# 06_-_Voltage_Sense.net
KiCad netlist of a schematic drawn in Altium Designer
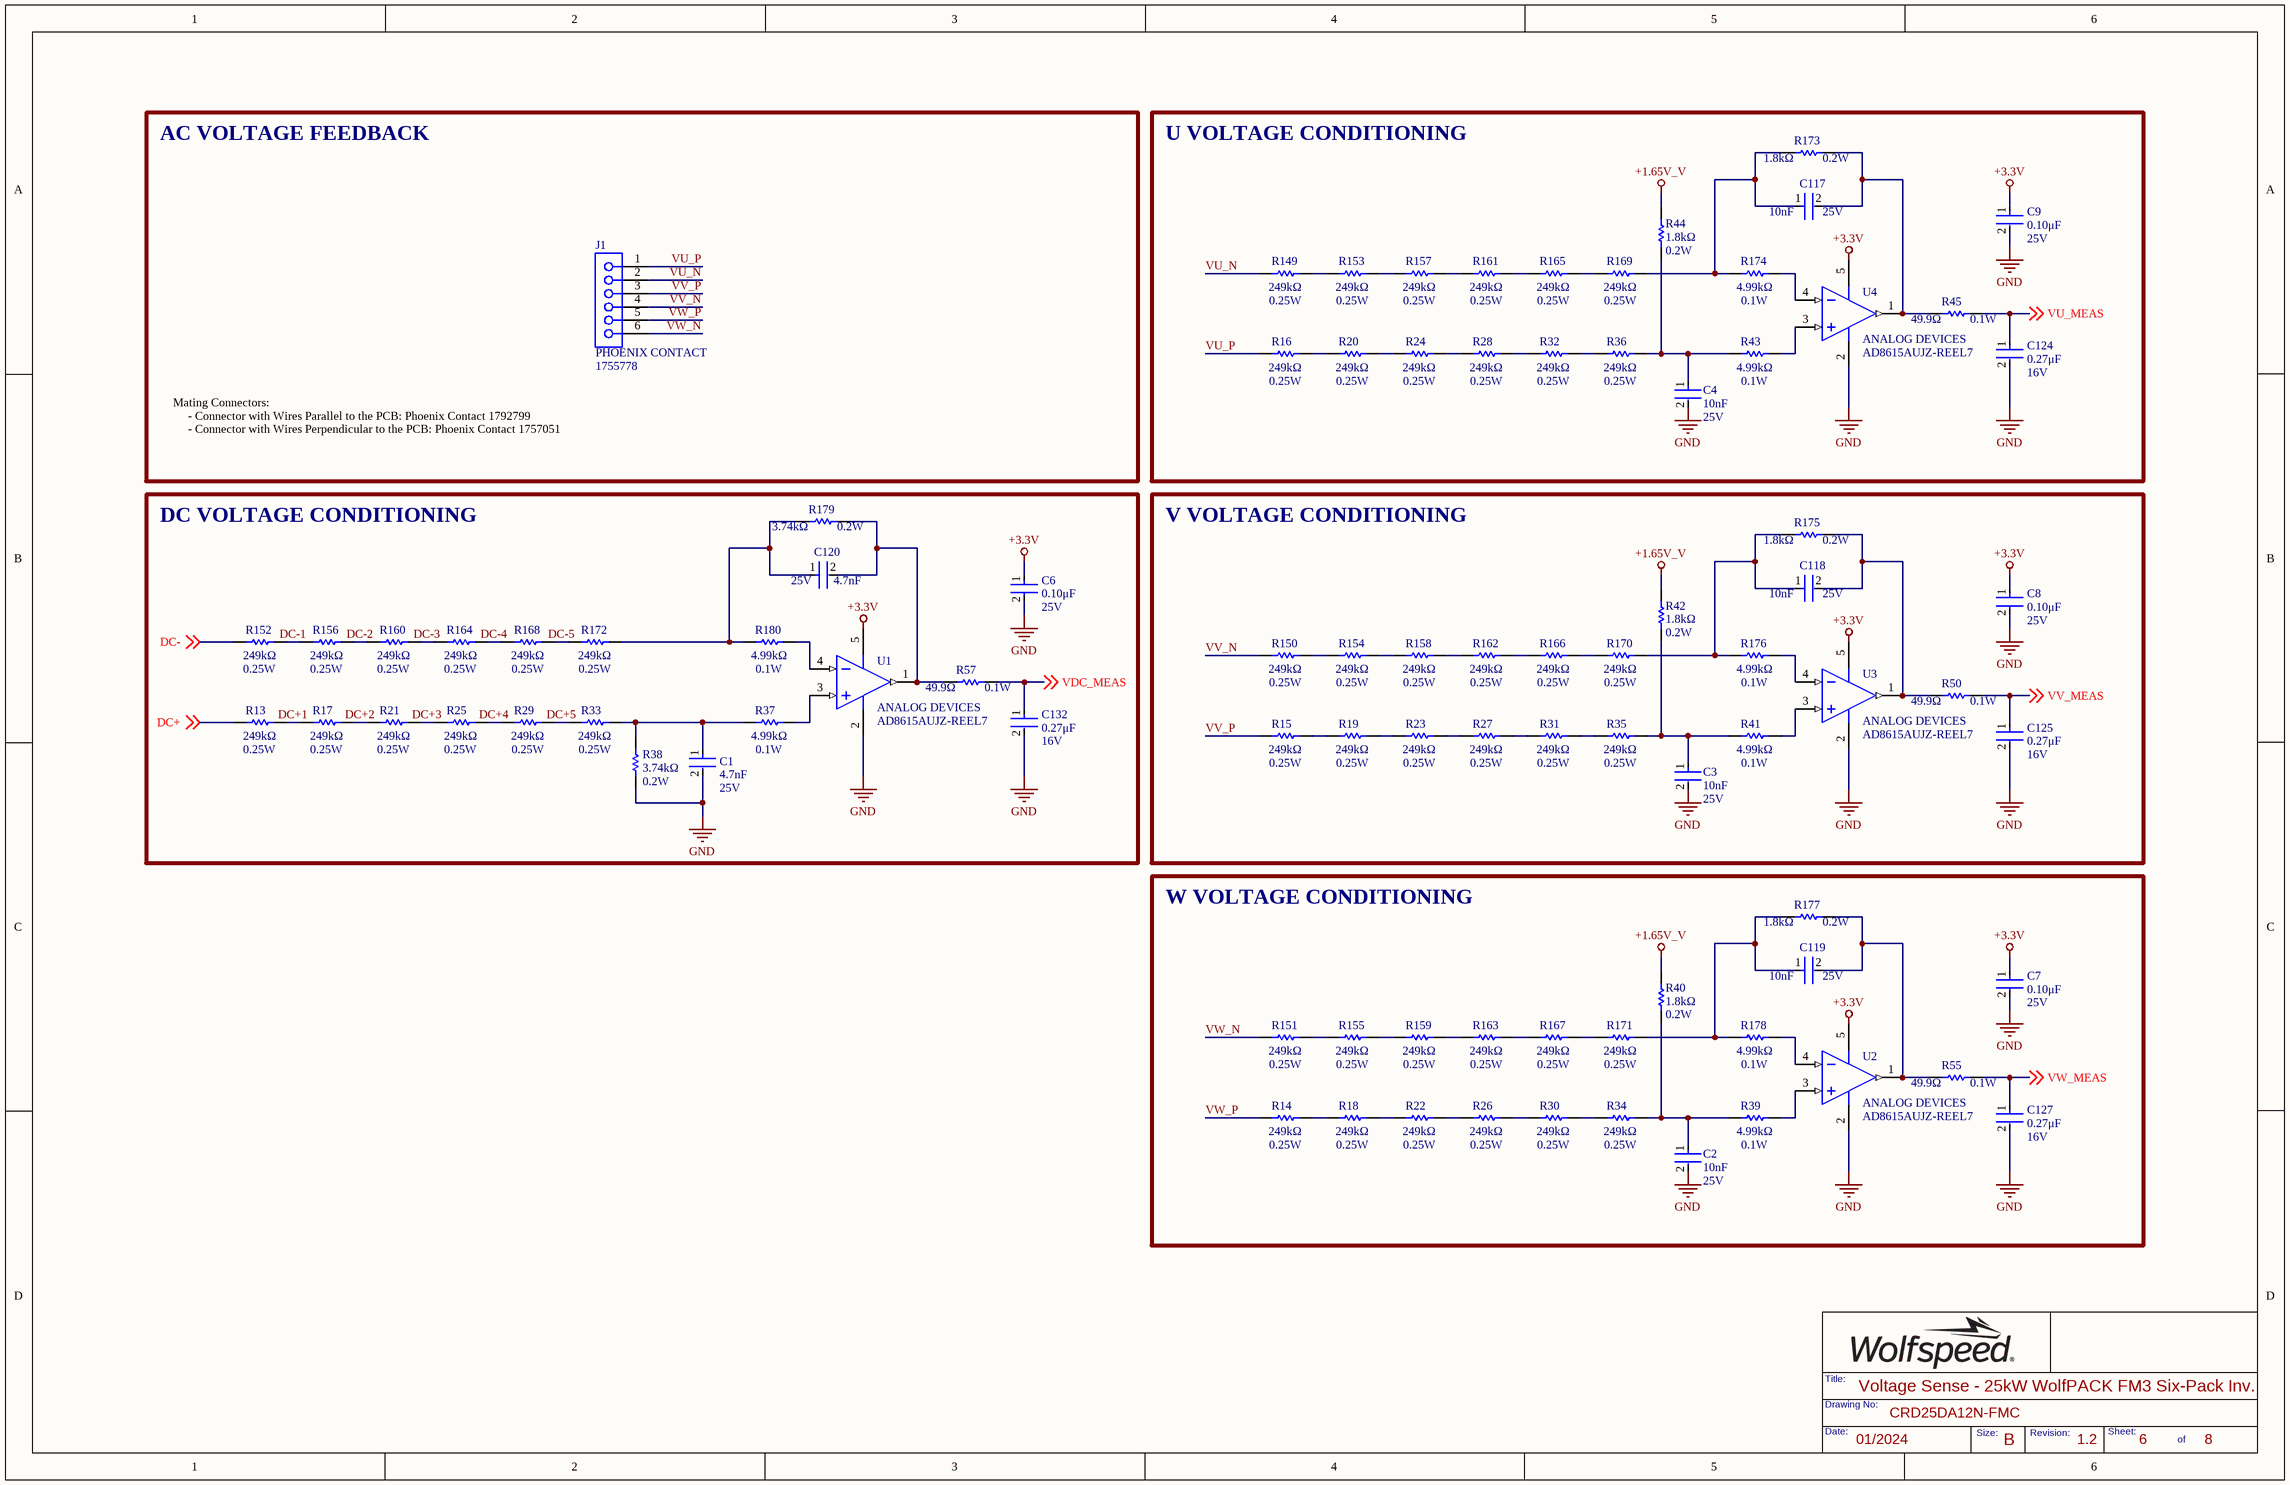
[diagram p0: 06 - Voltage Sense.SchDoc]

(export (version "E")
  (design (tool "Eeschema 10.0.6"))
  (components
    (comp (ref "C1")
      (value "C0603C472K3RAC7867")
      (footprint "FP-C0603C-CF-IPC_B")
      (description "CAP CER 4700PF 25V 10% X7R 0603")
      (fields
        (field (name "MANUFACTURER") "KEMET")
        (field (name "MANUFACTURER PART NUMBER") "C0603C472K3RACTU")
        (field (name "VOLTAGE RATING") "25V")
        (field (name "CAPACITANCE") "4.7nF")
      )
      (libsource (lib "Inverter_25kW") (part "C0603C472K3RAC7867"))
    )
    (comp (ref "C2")
      (value "10nF")
      (footprint "FP-C0603C-CF-IPC_B")
      (description "CAP CER 10000PF 25V X7R 0603")
      (fields
        (field (name "MANUFACTURER") "SAMSUNG")
        (field (name "MANUFACTURER PART NUMBER") "CL10B103KA8WPNC")
        (field (name "VOLTAGE RATING") "25V")
      )
      (libsource (lib "Inverter_25kW") (part "CL10B103KA8WPNC"))
    )
    (comp (ref "C3")
      (value "10nF")
      (footprint "FP-C0603C-CF-IPC_B")
      (description "CAP CER 10000PF 25V X7R 0603")
      (fields
        (field (name "MANUFACTURER") "SAMSUNG")
        (field (name "MANUFACTURER PART NUMBER") "CL10B103KA8WPNC")
        (field (name "VOLTAGE RATING") "25V")
      )
      (libsource (lib "Inverter_25kW") (part "CL10B103KA8WPNC"))
    )
    (comp (ref "C4")
      (value "10nF")
      (footprint "FP-C0603C-CF-IPC_B")
      (description "CAP CER 10000PF 25V X7R 0603")
      (fields
        (field (name "MANUFACTURER") "SAMSUNG")
        (field (name "MANUFACTURER PART NUMBER") "CL10B103KA8WPNC")
        (field (name "VOLTAGE RATING") "25V")
      )
      (libsource (lib "Inverter_25kW") (part "CL10B103KA8WPNC"))
    )
    (comp (ref "C6")
      (value "C0603C104K3RACTU")
      (footprint "FP-C0603C-CF-IPC_B")
      (description "CAP CER 0.1UF 25V X7R 0603")
      (fields
        (field (name "VOLTAGE RATING") "25V")
        (field (name "OCTOPART") "https://octopart.com/c0603c104k3ractu-kemet-127541")
        (field (name "MANUFACTURER") "KEMET")
        (field (name "CAPACITANCE") "0.10μF")
      )
      (libsource (lib "Altium Content Vault") (part "b4654b650e69147ec39a6b967a45e02"))
    )
    (comp (ref "C7")
      (value "C0603C104K3RACTU")
      (footprint "FP-C0603C-CF-IPC_B")
      (description "CAP CER 0.1UF 25V X7R 0603")
      (fields
        (field (name "VOLTAGE RATING") "25V")
        (field (name "OCTOPART") "https://octopart.com/c0603c104k3ractu-kemet-127541")
        (field (name "MANUFACTURER") "KEMET")
        (field (name "CAPACITANCE") "0.10μF")
      )
      (libsource (lib "Altium Content Vault") (part "b4654b650e69147ec39a6b967a45e02"))
    )
    (comp (ref "C8")
      (value "C0603C104K3RACTU")
      (footprint "FP-C0603C-CF-IPC_B")
      (description "CAP CER 0.1UF 25V X7R 0603")
      (fields
        (field (name "VOLTAGE RATING") "25V")
        (field (name "OCTOPART") "https://octopart.com/c0603c104k3ractu-kemet-127541")
        (field (name "MANUFACTURER") "KEMET")
        (field (name "CAPACITANCE") "0.10μF")
      )
      (libsource (lib "Altium Content Vault") (part "b4654b650e69147ec39a6b967a45e02"))
    )
    (comp (ref "C9")
      (value "C0603C104K3RACTU")
      (footprint "FP-C0603C-CF-IPC_B")
      (description "CAP CER 0.1UF 25V X7R 0603")
      (fields
        (field (name "VOLTAGE RATING") "25V")
        (field (name "OCTOPART") "https://octopart.com/c0603c104k3ractu-kemet-127541")
        (field (name "MANUFACTURER") "KEMET")
        (field (name "CAPACITANCE") "0.10μF")
      )
      (libsource (lib "Altium Content Vault") (part "b4654b650e69147ec39a6b967a45e02"))
    )
    (comp (ref "C117")
      (value "10nF")
      (footprint "FP-C0603C-CF-IPC_B")
      (description "CAP CER 10000PF 25V X7R 0603")
      (fields
        (field (name "MANUFACTURER") "SAMSUNG")
        (field (name "MANUFACTURER PART NUMBER") "CL10B103KA8WPNC")
        (field (name "VOLTAGE RATING") "25V")
      )
      (libsource (lib "Inverter_25kW") (part "CL10B103KA8WPNC"))
    )
    (comp (ref "C118")
      (value "10nF")
      (footprint "FP-C0603C-CF-IPC_B")
      (description "CAP CER 10000PF 25V X7R 0603")
      (fields
        (field (name "MANUFACTURER") "SAMSUNG")
        (field (name "MANUFACTURER PART NUMBER") "CL10B103KA8WPNC")
        (field (name "VOLTAGE RATING") "25V")
      )
      (libsource (lib "Inverter_25kW") (part "CL10B103KA8WPNC"))
    )
    (comp (ref "C119")
      (value "10nF")
      (footprint "FP-C0603C-CF-IPC_B")
      (description "CAP CER 10000PF 25V X7R 0603")
      (fields
        (field (name "MANUFACTURER") "SAMSUNG")
        (field (name "MANUFACTURER PART NUMBER") "CL10B103KA8WPNC")
        (field (name "VOLTAGE RATING") "25V")
      )
      (libsource (lib "Inverter_25kW") (part "CL10B103KA8WPNC"))
    )
    (comp (ref "C120")
      (value "C0603C472K3RAC7867")
      (footprint "FP-C0603C-CF-IPC_B")
      (description "CAP CER 4700PF 25V 10% X7R 0603")
      (fields
        (field (name "MANUFACTURER") "KEMET")
        (field (name "MANUFACTURER PART NUMBER") "C0603C472K3RACTU")
        (field (name "VOLTAGE RATING") "25V")
        (field (name "CAPACITANCE") "4.7nF")
      )
      (libsource (lib "Inverter_25kW") (part "C0603C472K3RAC7867"))
    )
    (comp (ref "C124")
      (value "GCM188R71C274KA37D")
      (footprint "FP-GCM188-0_1-IPC_A")
      (description "CAP CER 0.27UF 16V X7R 0603")
      (fields
        (field (name "VOLTAGE RATING (DC)") "16V")
        (field (name "CAPACITANCE") "0.27μF")
        (field (name "TOLERANCE") "10%")
        (field (name "MANUFACTURER") "MURATA")
      )
      (libsource (lib "Altium Content Vault") (part "02cd4be3c70576c341d710602a673aa"))
    )
    (comp (ref "C125")
      (value "GCM188R71C274KA37D")
      (footprint "FP-GCM188-0_1-IPC_A")
      (description "CAP CER 0.27UF 16V X7R 0603")
      (fields
        (field (name "VOLTAGE RATING (DC)") "16V")
        (field (name "CAPACITANCE") "0.27μF")
        (field (name "TOLERANCE") "10%")
        (field (name "MANUFACTURER") "MURATA")
      )
      (libsource (lib "Altium Content Vault") (part "02cd4be3c70576c341d710602a673aa"))
    )
    (comp (ref "C127")
      (value "GCM188R71C274KA37D")
      (footprint "FP-GCM188-0_1-IPC_A")
      (description "CAP CER 0.27UF 16V X7R 0603")
      (fields
        (field (name "VOLTAGE RATING (DC)") "16V")
        (field (name "CAPACITANCE") "0.27μF")
        (field (name "TOLERANCE") "10%")
        (field (name "MANUFACTURER") "MURATA")
      )
      (libsource (lib "Altium Content Vault") (part "02cd4be3c70576c341d710602a673aa"))
    )
    (comp (ref "C132")
      (value "GCM188R71C274KA37D")
      (footprint "FP-GCM188-0_1-IPC_A")
      (description "CAP CER 0.27UF 16V X7R 0603")
      (fields
        (field (name "VOLTAGE RATING (DC)") "16V")
        (field (name "CAPACITANCE") "0.27μF")
        (field (name "TOLERANCE") "10%")
        (field (name "MANUFACTURER") "MURATA")
      )
      (libsource (lib "Altium Content Vault") (part "02cd4be3c70576c341d710602a673aa"))
    )
    (comp (ref "J1")
      (value "1755778")
      (footprint "Inverter_25kW:1755778")
      (description "TERM BLOCK HDR 6POS VERT 5.08MM")
      (fields
        (field (name "MANUFACTURER") "PHOENIX CONTACT")
        (field (name "VOLTAGE") "300V")
        (field (name "MANUFACTURER PRINT") "PHOENIX CONTACT")
      )
      (libsource (lib "Inverter_25kW") (part "1755778"))
    )
    (comp (ref "R13")
      (value "TNPW1206249KBEEA")
      (footprint "RESC3216X65X50NL15T25")
      (description "RES 249K OHM 0.1% 1/4W 1206")
      (fields
        (field (name "MANUFACTURER") "VISHAY DALE")
        (field (name "RESISTANCE") "249kΩ")
        (field (name "POWER") "0.25W")
      )
      (libsource (lib "Altium Content Vault") (part "RES"))
    )
    (comp (ref "R14")
      (value "TNPW1206249KBEEA")
      (footprint "RESC3216X65X50NL15T25")
      (description "RES 249K OHM 0.1% 1/4W 1206")
      (fields
        (field (name "MANUFACTURER") "VISHAY DALE")
        (field (name "RESISTANCE") "249kΩ")
        (field (name "POWER") "0.25W")
      )
      (libsource (lib "Altium Content Vault") (part "RES"))
    )
    (comp (ref "R15")
      (value "TNPW1206249KBEEA")
      (footprint "RESC3216X65X50NL15T25")
      (description "RES 249K OHM 0.1% 1/4W 1206")
      (fields
        (field (name "MANUFACTURER") "VISHAY DALE")
        (field (name "RESISTANCE") "249kΩ")
        (field (name "POWER") "0.25W")
      )
      (libsource (lib "Altium Content Vault") (part "RES"))
    )
    (comp (ref "R16")
      (value "TNPW1206249KBEEA")
      (footprint "RESC3216X65X50NL15T25")
      (description "RES 249K OHM 0.1% 1/4W 1206")
      (fields
        (field (name "MANUFACTURER") "VISHAY DALE")
        (field (name "RESISTANCE") "249kΩ")
        (field (name "POWER") "0.25W")
      )
      (libsource (lib "Altium Content Vault") (part "RES"))
    )
    (comp (ref "R17")
      (value "TNPW1206249KBEEA")
      (footprint "RESC3216X65X50NL15T25")
      (description "RES 249K OHM 0.1% 1/4W 1206")
      (fields
        (field (name "MANUFACTURER") "VISHAY DALE")
        (field (name "RESISTANCE") "249kΩ")
        (field (name "POWER") "0.25W")
      )
      (libsource (lib "Altium Content Vault") (part "RES"))
    )
    (comp (ref "R18")
      (value "TNPW1206249KBEEA")
      (footprint "RESC3216X65X50NL15T25")
      (description "RES 249K OHM 0.1% 1/4W 1206")
      (fields
        (field (name "MANUFACTURER") "VISHAY DALE")
        (field (name "RESISTANCE") "249kΩ")
        (field (name "POWER") "0.25W")
      )
      (libsource (lib "Altium Content Vault") (part "RES"))
    )
    (comp (ref "R19")
      (value "TNPW1206249KBEEA")
      (footprint "RESC3216X65X50NL15T25")
      (description "RES 249K OHM 0.1% 1/4W 1206")
      (fields
        (field (name "MANUFACTURER") "VISHAY DALE")
        (field (name "RESISTANCE") "249kΩ")
        (field (name "POWER") "0.25W")
      )
      (libsource (lib "Altium Content Vault") (part "RES"))
    )
    (comp (ref "R20")
      (value "TNPW1206249KBEEA")
      (footprint "RESC3216X65X50NL15T25")
      (description "RES 249K OHM 0.1% 1/4W 1206")
      (fields
        (field (name "MANUFACTURER") "VISHAY DALE")
        (field (name "RESISTANCE") "249kΩ")
        (field (name "POWER") "0.25W")
      )
      (libsource (lib "Altium Content Vault") (part "RES"))
    )
    (comp (ref "R21")
      (value "TNPW1206249KBEEA")
      (footprint "RESC3216X65X50NL15T25")
      (description "RES 249K OHM 0.1% 1/4W 1206")
      (fields
        (field (name "MANUFACTURER") "VISHAY DALE")
        (field (name "RESISTANCE") "249kΩ")
        (field (name "POWER") "0.25W")
      )
      (libsource (lib "Altium Content Vault") (part "RES"))
    )
    (comp (ref "R22")
      (value "TNPW1206249KBEEA")
      (footprint "RESC3216X65X50NL15T25")
      (description "RES 249K OHM 0.1% 1/4W 1206")
      (fields
        (field (name "MANUFACTURER") "VISHAY DALE")
        (field (name "RESISTANCE") "249kΩ")
        (field (name "POWER") "0.25W")
      )
      (libsource (lib "Altium Content Vault") (part "RES"))
    )
    (comp (ref "R23")
      (value "TNPW1206249KBEEA")
      (footprint "RESC3216X65X50NL15T25")
      (description "RES 249K OHM 0.1% 1/4W 1206")
      (fields
        (field (name "MANUFACTURER") "VISHAY DALE")
        (field (name "RESISTANCE") "249kΩ")
        (field (name "POWER") "0.25W")
      )
      (libsource (lib "Altium Content Vault") (part "RES"))
    )
    (comp (ref "R24")
      (value "TNPW1206249KBEEA")
      (footprint "RESC3216X65X50NL15T25")
      (description "RES 249K OHM 0.1% 1/4W 1206")
      (fields
        (field (name "MANUFACTURER") "VISHAY DALE")
        (field (name "RESISTANCE") "249kΩ")
        (field (name "POWER") "0.25W")
      )
      (libsource (lib "Altium Content Vault") (part "RES"))
    )
    (comp (ref "R25")
      (value "TNPW1206249KBEEA")
      (footprint "RESC3216X65X50NL15T25")
      (description "RES 249K OHM 0.1% 1/4W 1206")
      (fields
        (field (name "MANUFACTURER") "VISHAY DALE")
        (field (name "RESISTANCE") "249kΩ")
        (field (name "POWER") "0.25W")
      )
      (libsource (lib "Altium Content Vault") (part "RES"))
    )
    (comp (ref "R26")
      (value "TNPW1206249KBEEA")
      (footprint "RESC3216X65X50NL15T25")
      (description "RES 249K OHM 0.1% 1/4W 1206")
      (fields
        (field (name "MANUFACTURER") "VISHAY DALE")
        (field (name "RESISTANCE") "249kΩ")
        (field (name "POWER") "0.25W")
      )
      (libsource (lib "Altium Content Vault") (part "RES"))
    )
    (comp (ref "R27")
      (value "TNPW1206249KBEEA")
      (footprint "RESC3216X65X50NL15T25")
      (description "RES 249K OHM 0.1% 1/4W 1206")
      (fields
        (field (name "MANUFACTURER") "VISHAY DALE")
        (field (name "RESISTANCE") "249kΩ")
        (field (name "POWER") "0.25W")
      )
      (libsource (lib "Altium Content Vault") (part "RES"))
    )
    (comp (ref "R28")
      (value "TNPW1206249KBEEA")
      (footprint "RESC3216X65X50NL15T25")
      (description "RES 249K OHM 0.1% 1/4W 1206")
      (fields
        (field (name "MANUFACTURER") "VISHAY DALE")
        (field (name "RESISTANCE") "249kΩ")
        (field (name "POWER") "0.25W")
      )
      (libsource (lib "Altium Content Vault") (part "RES"))
    )
    (comp (ref "R29")
      (value "TNPW1206249KBEEA")
      (footprint "RESC3216X65X50NL15T25")
      (description "RES 249K OHM 0.1% 1/4W 1206")
      (fields
        (field (name "MANUFACTURER") "VISHAY DALE")
        (field (name "RESISTANCE") "249kΩ")
        (field (name "POWER") "0.25W")
      )
      (libsource (lib "Altium Content Vault") (part "RES"))
    )
    (comp (ref "R30")
      (value "TNPW1206249KBEEA")
      (footprint "RESC3216X65X50NL15T25")
      (description "RES 249K OHM 0.1% 1/4W 1206")
      (fields
        (field (name "MANUFACTURER") "VISHAY DALE")
        (field (name "RESISTANCE") "249kΩ")
        (field (name "POWER") "0.25W")
      )
      (libsource (lib "Altium Content Vault") (part "RES"))
    )
    (comp (ref "R31")
      (value "TNPW1206249KBEEA")
      (footprint "RESC3216X65X50NL15T25")
      (description "RES 249K OHM 0.1% 1/4W 1206")
      (fields
        (field (name "MANUFACTURER") "VISHAY DALE")
        (field (name "RESISTANCE") "249kΩ")
        (field (name "POWER") "0.25W")
      )
      (libsource (lib "Altium Content Vault") (part "RES"))
    )
    (comp (ref "R32")
      (value "TNPW1206249KBEEA")
      (footprint "RESC3216X65X50NL15T25")
      (description "RES 249K OHM 0.1% 1/4W 1206")
      (fields
        (field (name "MANUFACTURER") "VISHAY DALE")
        (field (name "RESISTANCE") "249kΩ")
        (field (name "POWER") "0.25W")
      )
      (libsource (lib "Altium Content Vault") (part "RES"))
    )
    (comp (ref "R33")
      (value "TNPW1206249KBEEA")
      (footprint "RESC3216X65X50NL15T25")
      (description "RES 249K OHM 0.1% 1/4W 1206")
      (fields
        (field (name "MANUFACTURER") "VISHAY DALE")
        (field (name "RESISTANCE") "249kΩ")
        (field (name "POWER") "0.25W")
      )
      (libsource (lib "Altium Content Vault") (part "RES"))
    )
    (comp (ref "R34")
      (value "TNPW1206249KBEEA")
      (footprint "RESC3216X65X50NL15T25")
      (description "RES 249K OHM 0.1% 1/4W 1206")
      (fields
        (field (name "MANUFACTURER") "VISHAY DALE")
        (field (name "RESISTANCE") "249kΩ")
        (field (name "POWER") "0.25W")
      )
      (libsource (lib "Altium Content Vault") (part "RES"))
    )
    (comp (ref "R35")
      (value "TNPW1206249KBEEA")
      (footprint "RESC3216X65X50NL15T25")
      (description "RES 249K OHM 0.1% 1/4W 1206")
      (fields
        (field (name "MANUFACTURER") "VISHAY DALE")
        (field (name "RESISTANCE") "249kΩ")
        (field (name "POWER") "0.25W")
      )
      (libsource (lib "Altium Content Vault") (part "RES"))
    )
    (comp (ref "R36")
      (value "TNPW1206249KBEEA")
      (footprint "RESC3216X65X50NL15T25")
      (description "RES 249K OHM 0.1% 1/4W 1206")
      (fields
        (field (name "MANUFACTURER") "VISHAY DALE")
        (field (name "RESISTANCE") "249kΩ")
        (field (name "POWER") "0.25W")
      )
      (libsource (lib "Altium Content Vault") (part "RES"))
    )
    (comp (ref "R37")
      (value "RC0603FR-074K99L")
      (footprint "FP-MCR03-IPC_B")
      (description "RES 4.99K OHM 1% 1/10W 0603")
      (fields
        (field (name "MANUFACTURER") "YAGEO")
        (field (name "TOLERANCE") "1%")
        (field (name "POWER RATING") "0.1W")
        (field (name "RESISTANCE") "4.99kΩ")
      )
      (libsource (lib "Inverter_25kW") (part "RC0603FR-074K99L"))
    )
    (comp (ref "R38")
      (value "ERJ-PB3B3741V")
      (footprint "FP-MCR03-IPC_B")
      (description "RES SMD 3.74K OHM 0.1% 1/5W 0603")
      (fields
        (field (name "MANUFACTURER") "PANASONIC")
        (field (name "TOLERANCE") "0.1%")
        (field (name "MAX POWER DISSIPATION") "0.2W")
        (field (name "RESISTANCE") "3.74kΩ")
      )
      (libsource (lib "Inverter_25kW") (part "ERJ-PB3B3741V"))
    )
    (comp (ref "R39")
      (value "RC0603FR-074K99L")
      (footprint "FP-MCR03-IPC_B")
      (description "RES 4.99K OHM 1% 1/10W 0603")
      (fields
        (field (name "MANUFACTURER") "YAGEO")
        (field (name "TOLERANCE") "1%")
        (field (name "POWER RATING") "0.1W")
        (field (name "RESISTANCE") "4.99kΩ")
      )
      (libsource (lib "Inverter_25kW") (part "RC0603FR-074K99L"))
    )
    (comp (ref "R40")
      (value "ERJ-PB3B1801V")
      (footprint "FP-MCR03-IPC_B")
      (description "RES SMD 1.8K OHM 0.1% 1/5W 0603")
      (fields
        (field (name "MANUFACTURER") "PANASONIC")
        (field (name "TOLERANCE") "0.1%")
        (field (name "RESISTANCE") "1.8kΩ")
        (field (name "MAX POWER DISSIPATION") "0.2W")
      )
      (libsource (lib "Inverter_25kW") (part "ERJ-PB3B1801V"))
    )
    (comp (ref "R41")
      (value "RC0603FR-074K99L")
      (footprint "FP-MCR03-IPC_B")
      (description "RES 4.99K OHM 1% 1/10W 0603")
      (fields
        (field (name "MANUFACTURER") "YAGEO")
        (field (name "TOLERANCE") "1%")
        (field (name "POWER RATING") "0.1W")
        (field (name "RESISTANCE") "4.99kΩ")
      )
      (libsource (lib "Inverter_25kW") (part "RC0603FR-074K99L"))
    )
    (comp (ref "R42")
      (value "ERJ-PB3B1801V")
      (footprint "FP-MCR03-IPC_B")
      (description "RES SMD 1.8K OHM 0.1% 1/5W 0603")
      (fields
        (field (name "MANUFACTURER") "PANASONIC")
        (field (name "TOLERANCE") "0.1%")
        (field (name "RESISTANCE") "1.8kΩ")
        (field (name "MAX POWER DISSIPATION") "0.2W")
      )
      (libsource (lib "Inverter_25kW") (part "ERJ-PB3B1801V"))
    )
    (comp (ref "R43")
      (value "RC0603FR-074K99L")
      (footprint "FP-MCR03-IPC_B")
      (description "RES 4.99K OHM 1% 1/10W 0603")
      (fields
        (field (name "MANUFACTURER") "YAGEO")
        (field (name "TOLERANCE") "1%")
        (field (name "POWER RATING") "0.1W")
        (field (name "RESISTANCE") "4.99kΩ")
      )
      (libsource (lib "Inverter_25kW") (part "RC0603FR-074K99L"))
    )
    (comp (ref "R44")
      (value "ERJ-PB3B1801V")
      (footprint "FP-MCR03-IPC_B")
      (description "RES SMD 1.8K OHM 0.1% 1/5W 0603")
      (fields
        (field (name "MANUFACTURER") "PANASONIC")
        (field (name "TOLERANCE") "0.1%")
        (field (name "RESISTANCE") "1.8kΩ")
        (field (name "MAX POWER DISSIPATION") "0.2W")
      )
      (libsource (lib "Inverter_25kW") (part "ERJ-PB3B1801V"))
    )
    (comp (ref "R45")
      (value "ERJ-3EKF49R9V")
      (footprint "FP-MCR03-IPC_B")
      (description "RES SMD 49.9 OHM 1% 1/10W 0603")
      (fields
        (field (name "MANUFACTURER") "PANASONIC")
        (field (name "TOLERANCE") "1%")
        (field (name "RESISTANCE") "49.9Ω")
        (field (name "POWER RATING") "0.1W")
      )
      (libsource (lib "Inverter_25kW") (part "ERJ-3EKF49R9V"))
    )
    (comp (ref "R50")
      (value "ERJ-3EKF49R9V")
      (footprint "FP-MCR03-IPC_B")
      (description "RES SMD 49.9 OHM 1% 1/10W 0603")
      (fields
        (field (name "MANUFACTURER") "PANASONIC")
        (field (name "TOLERANCE") "1%")
        (field (name "RESISTANCE") "49.9Ω")
        (field (name "POWER RATING") "0.1W")
      )
      (libsource (lib "Inverter_25kW") (part "ERJ-3EKF49R9V"))
    )
    (comp (ref "R55")
      (value "ERJ-3EKF49R9V")
      (footprint "FP-MCR03-IPC_B")
      (description "RES SMD 49.9 OHM 1% 1/10W 0603")
      (fields
        (field (name "MANUFACTURER") "PANASONIC")
        (field (name "TOLERANCE") "1%")
        (field (name "RESISTANCE") "49.9Ω")
        (field (name "POWER RATING") "0.1W")
      )
      (libsource (lib "Inverter_25kW") (part "ERJ-3EKF49R9V"))
    )
    (comp (ref "R57")
      (value "ERJ-3EKF49R9V")
      (footprint "FP-MCR03-IPC_B")
      (description "RES SMD 49.9 OHM 1% 1/10W 0603")
      (fields
        (field (name "MANUFACTURER") "PANASONIC")
        (field (name "TOLERANCE") "1%")
        (field (name "RESISTANCE") "49.9Ω")
        (field (name "POWER RATING") "0.1W")
      )
      (libsource (lib "Inverter_25kW") (part "ERJ-3EKF49R9V"))
    )
    (comp (ref "R149")
      (value "TNPW1206249KBEEA")
      (footprint "RESC3216X65X50NL15T25")
      (description "RES 249K OHM 0.1% 1/4W 1206")
      (fields
        (field (name "MANUFACTURER") "VISHAY DALE")
        (field (name "RESISTANCE") "249kΩ")
        (field (name "POWER") "0.25W")
      )
      (libsource (lib "Altium Content Vault") (part "RES"))
    )
    (comp (ref "R150")
      (value "TNPW1206249KBEEA")
      (footprint "RESC3216X65X50NL15T25")
      (description "RES 249K OHM 0.1% 1/4W 1206")
      (fields
        (field (name "MANUFACTURER") "VISHAY DALE")
        (field (name "RESISTANCE") "249kΩ")
        (field (name "POWER") "0.25W")
      )
      (libsource (lib "Altium Content Vault") (part "RES"))
    )
    (comp (ref "R151")
      (value "TNPW1206249KBEEA")
      (footprint "RESC3216X65X50NL15T25")
      (description "RES 249K OHM 0.1% 1/4W 1206")
      (fields
        (field (name "MANUFACTURER") "VISHAY DALE")
        (field (name "RESISTANCE") "249kΩ")
        (field (name "POWER") "0.25W")
      )
      (libsource (lib "Altium Content Vault") (part "RES"))
    )
    (comp (ref "R152")
      (value "TNPW1206249KBEEA")
      (footprint "RESC3216X65X50NL15T25")
      (description "RES 249K OHM 0.1% 1/4W 1206")
      (fields
        (field (name "MANUFACTURER") "VISHAY DALE")
        (field (name "RESISTANCE") "249kΩ")
        (field (name "POWER") "0.25W")
      )
      (libsource (lib "Altium Content Vault") (part "RES"))
    )
    (comp (ref "R153")
      (value "TNPW1206249KBEEA")
      (footprint "RESC3216X65X50NL15T25")
      (description "RES 249K OHM 0.1% 1/4W 1206")
      (fields
        (field (name "MANUFACTURER") "VISHAY DALE")
        (field (name "RESISTANCE") "249kΩ")
        (field (name "POWER") "0.25W")
      )
      (libsource (lib "Altium Content Vault") (part "RES"))
    )
    (comp (ref "R154")
      (value "TNPW1206249KBEEA")
      (footprint "RESC3216X65X50NL15T25")
      (description "RES 249K OHM 0.1% 1/4W 1206")
      (fields
        (field (name "MANUFACTURER") "VISHAY DALE")
        (field (name "RESISTANCE") "249kΩ")
        (field (name "POWER") "0.25W")
      )
      (libsource (lib "Altium Content Vault") (part "RES"))
    )
    (comp (ref "R155")
      (value "TNPW1206249KBEEA")
      (footprint "RESC3216X65X50NL15T25")
      (description "RES 249K OHM 0.1% 1/4W 1206")
      (fields
        (field (name "MANUFACTURER") "VISHAY DALE")
        (field (name "RESISTANCE") "249kΩ")
        (field (name "POWER") "0.25W")
      )
      (libsource (lib "Altium Content Vault") (part "RES"))
    )
    (comp (ref "R156")
      (value "TNPW1206249KBEEA")
      (footprint "RESC3216X65X50NL15T25")
      (description "RES 249K OHM 0.1% 1/4W 1206")
      (fields
        (field (name "MANUFACTURER") "VISHAY DALE")
        (field (name "RESISTANCE") "249kΩ")
        (field (name "POWER") "0.25W")
      )
      (libsource (lib "Altium Content Vault") (part "RES"))
    )
    (comp (ref "R157")
      (value "TNPW1206249KBEEA")
      (footprint "RESC3216X65X50NL15T25")
      (description "RES 249K OHM 0.1% 1/4W 1206")
      (fields
        (field (name "MANUFACTURER") "VISHAY DALE")
        (field (name "RESISTANCE") "249kΩ")
        (field (name "POWER") "0.25W")
      )
      (libsource (lib "Altium Content Vault") (part "RES"))
    )
    (comp (ref "R158")
      (value "TNPW1206249KBEEA")
      (footprint "RESC3216X65X50NL15T25")
      (description "RES 249K OHM 0.1% 1/4W 1206")
      (fields
        (field (name "MANUFACTURER") "VISHAY DALE")
        (field (name "RESISTANCE") "249kΩ")
        (field (name "POWER") "0.25W")
      )
      (libsource (lib "Altium Content Vault") (part "RES"))
    )
    (comp (ref "R159")
      (value "TNPW1206249KBEEA")
      (footprint "RESC3216X65X50NL15T25")
      (description "RES 249K OHM 0.1% 1/4W 1206")
      (fields
        (field (name "MANUFACTURER") "VISHAY DALE")
        (field (name "RESISTANCE") "249kΩ")
        (field (name "POWER") "0.25W")
      )
      (libsource (lib "Altium Content Vault") (part "RES"))
    )
    (comp (ref "R160")
      (value "TNPW1206249KBEEA")
      (footprint "RESC3216X65X50NL15T25")
      (description "RES 249K OHM 0.1% 1/4W 1206")
      (fields
        (field (name "MANUFACTURER") "VISHAY DALE")
        (field (name "RESISTANCE") "249kΩ")
        (field (name "POWER") "0.25W")
      )
      (libsource (lib "Altium Content Vault") (part "RES"))
    )
    (comp (ref "R161")
      (value "TNPW1206249KBEEA")
      (footprint "RESC3216X65X50NL15T25")
      (description "RES 249K OHM 0.1% 1/4W 1206")
      (fields
        (field (name "MANUFACTURER") "VISHAY DALE")
        (field (name "RESISTANCE") "249kΩ")
        (field (name "POWER") "0.25W")
      )
      (libsource (lib "Altium Content Vault") (part "RES"))
    )
    (comp (ref "R162")
      (value "TNPW1206249KBEEA")
      (footprint "RESC3216X65X50NL15T25")
      (description "RES 249K OHM 0.1% 1/4W 1206")
      (fields
        (field (name "MANUFACTURER") "VISHAY DALE")
        (field (name "RESISTANCE") "249kΩ")
        (field (name "POWER") "0.25W")
      )
      (libsource (lib "Altium Content Vault") (part "RES"))
    )
    (comp (ref "R163")
      (value "TNPW1206249KBEEA")
      (footprint "RESC3216X65X50NL15T25")
      (description "RES 249K OHM 0.1% 1/4W 1206")
      (fields
        (field (name "MANUFACTURER") "VISHAY DALE")
        (field (name "RESISTANCE") "249kΩ")
        (field (name "POWER") "0.25W")
      )
      (libsource (lib "Altium Content Vault") (part "RES"))
    )
    (comp (ref "R164")
      (value "TNPW1206249KBEEA")
      (footprint "RESC3216X65X50NL15T25")
      (description "RES 249K OHM 0.1% 1/4W 1206")
      (fields
        (field (name "MANUFACTURER") "VISHAY DALE")
        (field (name "RESISTANCE") "249kΩ")
        (field (name "POWER") "0.25W")
      )
      (libsource (lib "Altium Content Vault") (part "RES"))
    )
    (comp (ref "R165")
      (value "TNPW1206249KBEEA")
      (footprint "RESC3216X65X50NL15T25")
      (description "RES 249K OHM 0.1% 1/4W 1206")
      (fields
        (field (name "MANUFACTURER") "VISHAY DALE")
        (field (name "RESISTANCE") "249kΩ")
        (field (name "POWER") "0.25W")
      )
      (libsource (lib "Altium Content Vault") (part "RES"))
    )
    (comp (ref "R166")
      (value "TNPW1206249KBEEA")
      (footprint "RESC3216X65X50NL15T25")
      (description "RES 249K OHM 0.1% 1/4W 1206")
      (fields
        (field (name "MANUFACTURER") "VISHAY DALE")
        (field (name "RESISTANCE") "249kΩ")
        (field (name "POWER") "0.25W")
      )
      (libsource (lib "Altium Content Vault") (part "RES"))
    )
    (comp (ref "R167")
      (value "TNPW1206249KBEEA")
      (footprint "RESC3216X65X50NL15T25")
      (description "RES 249K OHM 0.1% 1/4W 1206")
      (fields
        (field (name "MANUFACTURER") "VISHAY DALE")
        (field (name "RESISTANCE") "249kΩ")
        (field (name "POWER") "0.25W")
      )
      (libsource (lib "Altium Content Vault") (part "RES"))
    )
    (comp (ref "R168")
      (value "TNPW1206249KBEEA")
      (footprint "RESC3216X65X50NL15T25")
      (description "RES 249K OHM 0.1% 1/4W 1206")
      (fields
        (field (name "MANUFACTURER") "VISHAY DALE")
        (field (name "RESISTANCE") "249kΩ")
        (field (name "POWER") "0.25W")
      )
      (libsource (lib "Altium Content Vault") (part "RES"))
    )
    (comp (ref "R169")
      (value "TNPW1206249KBEEA")
      (footprint "RESC3216X65X50NL15T25")
      (description "RES 249K OHM 0.1% 1/4W 1206")
      (fields
        (field (name "MANUFACTURER") "VISHAY DALE")
        (field (name "RESISTANCE") "249kΩ")
        (field (name "POWER") "0.25W")
      )
      (libsource (lib "Altium Content Vault") (part "RES"))
    )
    (comp (ref "R170")
      (value "TNPW1206249KBEEA")
      (footprint "RESC3216X65X50NL15T25")
      (description "RES 249K OHM 0.1% 1/4W 1206")
      (fields
        (field (name "MANUFACTURER") "VISHAY DALE")
        (field (name "RESISTANCE") "249kΩ")
        (field (name "POWER") "0.25W")
      )
      (libsource (lib "Altium Content Vault") (part "RES"))
    )
    (comp (ref "R171")
      (value "TNPW1206249KBEEA")
      (footprint "RESC3216X65X50NL15T25")
      (description "RES 249K OHM 0.1% 1/4W 1206")
      (fields
        (field (name "MANUFACTURER") "VISHAY DALE")
        (field (name "RESISTANCE") "249kΩ")
        (field (name "POWER") "0.25W")
      )
      (libsource (lib "Altium Content Vault") (part "RES"))
    )
    (comp (ref "R172")
      (value "TNPW1206249KBEEA")
      (footprint "RESC3216X65X50NL15T25")
      (description "RES 249K OHM 0.1% 1/4W 1206")
      (fields
        (field (name "MANUFACTURER") "VISHAY DALE")
        (field (name "RESISTANCE") "249kΩ")
        (field (name "POWER") "0.25W")
      )
      (libsource (lib "Altium Content Vault") (part "RES"))
    )
    (comp (ref "R173")
      (value "ERJ-PB3B1801V")
      (footprint "FP-MCR03-IPC_B")
      (description "RES SMD 1.8K OHM 0.1% 1/5W 0603")
      (fields
        (field (name "MANUFACTURER") "PANASONIC")
        (field (name "TOLERANCE") "0.1%")
        (field (name "RESISTANCE") "1.8kΩ")
        (field (name "MAX POWER DISSIPATION") "0.2W")
      )
      (libsource (lib "Inverter_25kW") (part "ERJ-PB3B1801V"))
    )
    (comp (ref "R174")
      (value "RC0603FR-074K99L")
      (footprint "FP-MCR03-IPC_B")
      (description "RES 4.99K OHM 1% 1/10W 0603")
      (fields
        (field (name "MANUFACTURER") "YAGEO")
        (field (name "TOLERANCE") "1%")
        (field (name "POWER RATING") "0.1W")
        (field (name "RESISTANCE") "4.99kΩ")
      )
      (libsource (lib "Inverter_25kW") (part "RC0603FR-074K99L"))
    )
    (comp (ref "R175")
      (value "ERJ-PB3B1801V")
      (footprint "FP-MCR03-IPC_B")
      (description "RES SMD 1.8K OHM 0.1% 1/5W 0603")
      (fields
        (field (name "MANUFACTURER") "PANASONIC")
        (field (name "TOLERANCE") "0.1%")
        (field (name "RESISTANCE") "1.8kΩ")
        (field (name "MAX POWER DISSIPATION") "0.2W")
      )
      (libsource (lib "Inverter_25kW") (part "ERJ-PB3B1801V"))
    )
    (comp (ref "R176")
      (value "RC0603FR-074K99L")
      (footprint "FP-MCR03-IPC_B")
      (description "RES 4.99K OHM 1% 1/10W 0603")
      (fields
        (field (name "MANUFACTURER") "YAGEO")
        (field (name "TOLERANCE") "1%")
        (field (name "POWER RATING") "0.1W")
        (field (name "RESISTANCE") "4.99kΩ")
      )
      (libsource (lib "Inverter_25kW") (part "RC0603FR-074K99L"))
    )
    (comp (ref "R177")
      (value "ERJ-PB3B1801V")
      (footprint "FP-MCR03-IPC_B")
      (description "RES SMD 1.8K OHM 0.1% 1/5W 0603")
      (fields
        (field (name "MANUFACTURER") "PANASONIC")
        (field (name "TOLERANCE") "0.1%")
        (field (name "RESISTANCE") "1.8kΩ")
        (field (name "MAX POWER DISSIPATION") "0.2W")
      )
      (libsource (lib "Inverter_25kW") (part "ERJ-PB3B1801V"))
    )
    (comp (ref "R178")
      (value "RC0603FR-074K99L")
      (footprint "FP-MCR03-IPC_B")
      (description "RES 4.99K OHM 1% 1/10W 0603")
      (fields
        (field (name "MANUFACTURER") "YAGEO")
        (field (name "TOLERANCE") "1%")
        (field (name "POWER RATING") "0.1W")
        (field (name "RESISTANCE") "4.99kΩ")
      )
      (libsource (lib "Inverter_25kW") (part "RC0603FR-074K99L"))
    )
    (comp (ref "R179")
      (value "ERJ-PB3B3741V")
      (footprint "FP-MCR03-IPC_B")
      (description "RES SMD 3.74K OHM 0.1% 1/5W 0603")
      (fields
        (field (name "MANUFACTURER") "PANASONIC")
        (field (name "TOLERANCE") "0.1%")
        (field (name "MAX POWER DISSIPATION") "0.2W")
        (field (name "RESISTANCE") "3.74kΩ")
      )
      (libsource (lib "Inverter_25kW") (part "ERJ-PB3B3741V"))
    )
    (comp (ref "R180")
      (value "RC0603FR-074K99L")
      (footprint "FP-MCR03-IPC_B")
      (description "RES 4.99K OHM 1% 1/10W 0603")
      (fields
        (field (name "MANUFACTURER") "YAGEO")
        (field (name "TOLERANCE") "1%")
        (field (name "POWER RATING") "0.1W")
        (field (name "RESISTANCE") "4.99kΩ")
      )
      (libsource (lib "Inverter_25kW") (part "RC0603FR-074K99L"))
    )
    (comp (ref "U1")
      (value "AD8615AUJZ-REEL7")
      (footprint "ADI-UJ-5_M")
      (description "IC OPAMP GP 1 CIRCUIT TSOT23-5")
      (fields
        (field (name "MANUFACTURER") "ANALOG DEVICES")
        (field (name "GENERIC PART NUMBER") "AD8615")
        (field (name "MANUFACTURER PART NUMBER") "AD8615AUJZ-REEL7")
      )
      (libsource (lib "Altium Content Vault") (part "ADI-ADxxxx-X-5"))
    )
    (comp (ref "U2")
      (value "AD8615AUJZ-REEL7")
      (footprint "ADI-UJ-5_M")
      (description "IC OPAMP GP 1 CIRCUIT TSOT23-5")
      (fields
        (field (name "MANUFACTURER") "ANALOG DEVICES")
        (field (name "GENERIC PART NUMBER") "AD8615")
        (field (name "MANUFACTURER PART NUMBER") "AD8615AUJZ-REEL7")
      )
      (libsource (lib "Altium Content Vault") (part "ADI-ADxxxx-X-5"))
    )
    (comp (ref "U3")
      (value "AD8615AUJZ-REEL7")
      (footprint "ADI-UJ-5_M")
      (description "IC OPAMP GP 1 CIRCUIT TSOT23-5")
      (fields
        (field (name "MANUFACTURER") "ANALOG DEVICES")
        (field (name "GENERIC PART NUMBER") "AD8615")
        (field (name "MANUFACTURER PART NUMBER") "AD8615AUJZ-REEL7")
      )
      (libsource (lib "Altium Content Vault") (part "ADI-ADxxxx-X-5"))
    )
    (comp (ref "U4")
      (value "AD8615AUJZ-REEL7")
      (footprint "ADI-UJ-5_M")
      (description "IC OPAMP GP 1 CIRCUIT TSOT23-5")
      (fields
        (field (name "MANUFACTURER") "ANALOG DEVICES")
        (field (name "GENERIC PART NUMBER") "AD8615")
        (field (name "MANUFACTURER PART NUMBER") "AD8615AUJZ-REEL7")
      )
      (libsource (lib "Altium Content Vault") (part "ADI-ADxxxx-X-5"))
    )
  )
  (nets
    (net (code "1") (name "+1.65V_V") (class "Default")
      (node (ref "R40") (pin "2") (pinfunction "2_2") (pintype "passive"))
      (node (ref "R42") (pin "2") (pinfunction "2_2") (pintype "passive"))
      (node (ref "R44") (pin "2") (pinfunction "2_2") (pintype "passive"))
    )
    (net (code "2") (name "+3.3V") (class "Default")
      (node (ref "C6") (pin "1") (pinfunction "1_1") (pintype "passive"))
      (node (ref "C7") (pin "1") (pinfunction "1_1") (pintype "passive"))
      (node (ref "C8") (pin "1") (pinfunction "1_1") (pintype "passive"))
      (node (ref "C9") (pin "1") (pinfunction "1_1") (pintype "passive"))
      (node (ref "U1") (pin "5") (pinfunction "+V_5") (pintype "power_in"))
      (node (ref "U2") (pin "5") (pinfunction "+V_5") (pintype "power_in"))
      (node (ref "U3") (pin "5") (pinfunction "+V_5") (pintype "power_in"))
      (node (ref "U4") (pin "5") (pinfunction "+V_5") (pintype "power_in"))
    )
    (net (code "3") (name "/DC+1") (class "Default")
      (node (ref "R13") (pin "2") (pinfunction "2_2") (pintype "passive"))
      (node (ref "R17") (pin "1") (pinfunction "1_1") (pintype "passive"))
    )
    (net (code "4") (name "/DC+2") (class "Default")
      (node (ref "R17") (pin "2") (pinfunction "2_2") (pintype "passive"))
      (node (ref "R21") (pin "1") (pinfunction "1_1") (pintype "passive"))
    )
    (net (code "5") (name "/DC+3") (class "Default")
      (node (ref "R21") (pin "2") (pinfunction "2_2") (pintype "passive"))
      (node (ref "R25") (pin "1") (pinfunction "1_1") (pintype "passive"))
    )
    (net (code "6") (name "/DC+4") (class "Default")
      (node (ref "R25") (pin "2") (pinfunction "2_2") (pintype "passive"))
      (node (ref "R29") (pin "1") (pinfunction "1_1") (pintype "passive"))
    )
    (net (code "7") (name "/DC+5") (class "Default")
      (node (ref "R29") (pin "2") (pinfunction "2_2") (pintype "passive"))
      (node (ref "R33") (pin "1") (pinfunction "1_1") (pintype "passive"))
    )
    (net (code "8") (name "/DC-1") (class "Default")
      (node (ref "R152") (pin "2") (pinfunction "2_2") (pintype "passive"))
      (node (ref "R156") (pin "1") (pinfunction "1_1") (pintype "passive"))
    )
    (net (code "9") (name "/DC-2") (class "Default")
      (node (ref "R156") (pin "2") (pinfunction "2_2") (pintype "passive"))
      (node (ref "R160") (pin "1") (pinfunction "1_1") (pintype "passive"))
    )
    (net (code "10") (name "/DC-3") (class "Default")
      (node (ref "R160") (pin "2") (pinfunction "2_2") (pintype "passive"))
      (node (ref "R164") (pin "1") (pinfunction "1_1") (pintype "passive"))
    )
    (net (code "11") (name "/DC-4") (class "Default")
      (node (ref "R164") (pin "2") (pinfunction "2_2") (pintype "passive"))
      (node (ref "R168") (pin "1") (pinfunction "1_1") (pintype "passive"))
    )
    (net (code "12") (name "/DC-5") (class "Default")
      (node (ref "R168") (pin "2") (pinfunction "2_2") (pintype "passive"))
      (node (ref "R172") (pin "1") (pinfunction "1_1") (pintype "passive"))
    )
    (net (code "13") (name "/VU_N") (class "Default")
      (node (ref "J1") (pin "2") (pinfunction "2_2") (pintype "passive"))
      (node (ref "R149") (pin "1") (pinfunction "1_1") (pintype "passive"))
    )
    (net (code "14") (name "/VU_P") (class "Default")
      (node (ref "J1") (pin "1") (pinfunction "1_1") (pintype "passive"))
      (node (ref "R16") (pin "1") (pinfunction "1_1") (pintype "passive"))
    )
    (net (code "15") (name "/VV_N") (class "Default")
      (node (ref "J1") (pin "4") (pinfunction "4_4") (pintype "passive"))
      (node (ref "R150") (pin "1") (pinfunction "1_1") (pintype "passive"))
    )
    (net (code "16") (name "/VV_P") (class "Default")
      (node (ref "J1") (pin "3") (pinfunction "3_3") (pintype "passive"))
      (node (ref "R15") (pin "1") (pinfunction "1_1") (pintype "passive"))
    )
    (net (code "17") (name "/VW_N") (class "Default")
      (node (ref "J1") (pin "6") (pinfunction "6_6") (pintype "passive"))
      (node (ref "R151") (pin "1") (pinfunction "1_1") (pintype "passive"))
    )
    (net (code "18") (name "/VW_P") (class "Default")
      (node (ref "J1") (pin "5") (pinfunction "5_5") (pintype "passive"))
      (node (ref "R14") (pin "1") (pinfunction "1_1") (pintype "passive"))
    )
    (net (code "19") (name "DC+") (class "Default")
      (node (ref "R13") (pin "1") (pinfunction "1_1") (pintype "passive"))
    )
    (net (code "20") (name "DC-") (class "Default")
      (node (ref "R152") (pin "1") (pinfunction "1_1") (pintype "passive"))
    )
    (net (code "21") (name "GND") (class "Default")
      (node (ref "C1") (pin "2") (pinfunction "2_2") (pintype "passive"))
      (node (ref "C124") (pin "2") (pinfunction "2_2") (pintype "passive"))
      (node (ref "C125") (pin "2") (pinfunction "2_2") (pintype "passive"))
      (node (ref "C127") (pin "2") (pinfunction "2_2") (pintype "passive"))
      (node (ref "C132") (pin "2") (pinfunction "2_2") (pintype "passive"))
      (node (ref "C2") (pin "2") (pinfunction "2_2") (pintype "passive"))
      (node (ref "C3") (pin "2") (pinfunction "2_2") (pintype "passive"))
      (node (ref "C4") (pin "2") (pinfunction "2_2") (pintype "passive"))
      (node (ref "C6") (pin "2") (pinfunction "2_2") (pintype "passive"))
      (node (ref "C7") (pin "2") (pinfunction "2_2") (pintype "passive"))
      (node (ref "C8") (pin "2") (pinfunction "2_2") (pintype "passive"))
      (node (ref "C9") (pin "2") (pinfunction "2_2") (pintype "passive"))
      (node (ref "R38") (pin "1") (pinfunction "1_1") (pintype "passive"))
      (node (ref "U1") (pin "2") (pinfunction "-V_2") (pintype "power_in"))
      (node (ref "U2") (pin "2") (pinfunction "-V_2") (pintype "power_in"))
      (node (ref "U3") (pin "2") (pinfunction "-V_2") (pintype "power_in"))
      (node (ref "U4") (pin "2") (pinfunction "-V_2") (pintype "power_in"))
    )
    (net (code "22") (name "Net-(C1-Pad1)") (class "Default")
      (node (ref "C1") (pin "1") (pinfunction "1_1") (pintype "passive"))
      (node (ref "R33") (pin "2") (pinfunction "2_2") (pintype "passive"))
      (node (ref "R37") (pin "1") (pinfunction "1_1") (pintype "passive"))
      (node (ref "R38") (pin "2") (pinfunction "2_2") (pintype "passive"))
    )
    (net (code "23") (name "Net-(C2-Pad1)") (class "Default")
      (node (ref "C2") (pin "1") (pinfunction "1_1") (pintype "passive"))
      (node (ref "R34") (pin "2") (pinfunction "2_2") (pintype "passive"))
      (node (ref "R39") (pin "1") (pinfunction "1_1") (pintype "passive"))
      (node (ref "R40") (pin "1") (pinfunction "1_1") (pintype "passive"))
    )
    (net (code "24") (name "Net-(C3-Pad1)") (class "Default")
      (node (ref "C3") (pin "1") (pinfunction "1_1") (pintype "passive"))
      (node (ref "R35") (pin "2") (pinfunction "2_2") (pintype "passive"))
      (node (ref "R41") (pin "1") (pinfunction "1_1") (pintype "passive"))
      (node (ref "R42") (pin "1") (pinfunction "1_1") (pintype "passive"))
    )
    (net (code "25") (name "Net-(C4-Pad1)") (class "Default")
      (node (ref "C4") (pin "1") (pinfunction "1_1") (pintype "passive"))
      (node (ref "R36") (pin "2") (pinfunction "2_2") (pintype "passive"))
      (node (ref "R43") (pin "1") (pinfunction "1_1") (pintype "passive"))
      (node (ref "R44") (pin "1") (pinfunction "1_1") (pintype "passive"))
    )
    (net (code "26") (name "Net-(C117-Pad1)") (class "Default")
      (node (ref "C117") (pin "1") (pinfunction "1_1") (pintype "passive"))
      (node (ref "R169") (pin "2") (pinfunction "2_2") (pintype "passive"))
      (node (ref "R173") (pin "2") (pinfunction "2_2") (pintype "passive"))
      (node (ref "R174") (pin "1") (pinfunction "1_1") (pintype "passive"))
    )
    (net (code "27") (name "Net-(C118-Pad1)") (class "Default")
      (node (ref "C118") (pin "1") (pinfunction "1_1") (pintype "passive"))
      (node (ref "R170") (pin "2") (pinfunction "2_2") (pintype "passive"))
      (node (ref "R175") (pin "2") (pinfunction "2_2") (pintype "passive"))
      (node (ref "R176") (pin "1") (pinfunction "1_1") (pintype "passive"))
    )
    (net (code "28") (name "Net-(C119-Pad1)") (class "Default")
      (node (ref "C119") (pin "1") (pinfunction "1_1") (pintype "passive"))
      (node (ref "R171") (pin "2") (pinfunction "2_2") (pintype "passive"))
      (node (ref "R177") (pin "2") (pinfunction "2_2") (pintype "passive"))
      (node (ref "R178") (pin "1") (pinfunction "1_1") (pintype "passive"))
    )
    (net (code "29") (name "Net-(C120-Pad1)") (class "Default")
      (node (ref "C120") (pin "1") (pinfunction "1_1") (pintype "passive"))
      (node (ref "R172") (pin "2") (pinfunction "2_2") (pintype "passive"))
      (node (ref "R179") (pin "1") (pinfunction "1_1") (pintype "passive"))
      (node (ref "R180") (pin "1") (pinfunction "1_1") (pintype "passive"))
    )
    (net (code "30") (name "Net-(R14-Pad2)") (class "Default")
      (node (ref "R14") (pin "2") (pinfunction "2_2") (pintype "passive"))
      (node (ref "R18") (pin "1") (pinfunction "1_1") (pintype "passive"))
    )
    (net (code "31") (name "Net-(R15-Pad2)") (class "Default")
      (node (ref "R15") (pin "2") (pinfunction "2_2") (pintype "passive"))
      (node (ref "R19") (pin "1") (pinfunction "1_1") (pintype "passive"))
    )
    (net (code "32") (name "Net-(R16-Pad2)") (class "Default")
      (node (ref "R16") (pin "2") (pinfunction "2_2") (pintype "passive"))
      (node (ref "R20") (pin "1") (pinfunction "1_1") (pintype "passive"))
    )
    (net (code "33") (name "Net-(R18-Pad2)") (class "Default")
      (node (ref "R18") (pin "2") (pinfunction "2_2") (pintype "passive"))
      (node (ref "R22") (pin "1") (pinfunction "1_1") (pintype "passive"))
    )
    (net (code "34") (name "Net-(R19-Pad2)") (class "Default")
      (node (ref "R19") (pin "2") (pinfunction "2_2") (pintype "passive"))
      (node (ref "R23") (pin "1") (pinfunction "1_1") (pintype "passive"))
    )
    (net (code "35") (name "Net-(R20-Pad2)") (class "Default")
      (node (ref "R20") (pin "2") (pinfunction "2_2") (pintype "passive"))
      (node (ref "R24") (pin "1") (pinfunction "1_1") (pintype "passive"))
    )
    (net (code "36") (name "Net-(R22-Pad2)") (class "Default")
      (node (ref "R22") (pin "2") (pinfunction "2_2") (pintype "passive"))
      (node (ref "R26") (pin "1") (pinfunction "1_1") (pintype "passive"))
    )
    (net (code "37") (name "Net-(R23-Pad2)") (class "Default")
      (node (ref "R23") (pin "2") (pinfunction "2_2") (pintype "passive"))
      (node (ref "R27") (pin "1") (pinfunction "1_1") (pintype "passive"))
    )
    (net (code "38") (name "Net-(R24-Pad2)") (class "Default")
      (node (ref "R24") (pin "2") (pinfunction "2_2") (pintype "passive"))
      (node (ref "R28") (pin "1") (pinfunction "1_1") (pintype "passive"))
    )
    (net (code "39") (name "Net-(R26-Pad2)") (class "Default")
      (node (ref "R26") (pin "2") (pinfunction "2_2") (pintype "passive"))
      (node (ref "R30") (pin "1") (pinfunction "1_1") (pintype "passive"))
    )
    (net (code "40") (name "Net-(R27-Pad2)") (class "Default")
      (node (ref "R27") (pin "2") (pinfunction "2_2") (pintype "passive"))
      (node (ref "R31") (pin "1") (pinfunction "1_1") (pintype "passive"))
    )
    (net (code "41") (name "Net-(R28-Pad2)") (class "Default")
      (node (ref "R28") (pin "2") (pinfunction "2_2") (pintype "passive"))
      (node (ref "R32") (pin "1") (pinfunction "1_1") (pintype "passive"))
    )
    (net (code "42") (name "Net-(R30-Pad2)") (class "Default")
      (node (ref "R30") (pin "2") (pinfunction "2_2") (pintype "passive"))
      (node (ref "R34") (pin "1") (pinfunction "1_1") (pintype "passive"))
    )
    (net (code "43") (name "Net-(R31-Pad2)") (class "Default")
      (node (ref "R31") (pin "2") (pinfunction "2_2") (pintype "passive"))
      (node (ref "R35") (pin "1") (pinfunction "1_1") (pintype "passive"))
    )
    (net (code "44") (name "Net-(R32-Pad2)") (class "Default")
      (node (ref "R32") (pin "2") (pinfunction "2_2") (pintype "passive"))
      (node (ref "R36") (pin "1") (pinfunction "1_1") (pintype "passive"))
    )
    (net (code "45") (name "Net-(R149-Pad2)") (class "Default")
      (node (ref "R149") (pin "2") (pinfunction "2_2") (pintype "passive"))
      (node (ref "R153") (pin "1") (pinfunction "1_1") (pintype "passive"))
    )
    (net (code "46") (name "Net-(R150-Pad2)") (class "Default")
      (node (ref "R150") (pin "2") (pinfunction "2_2") (pintype "passive"))
      (node (ref "R154") (pin "1") (pinfunction "1_1") (pintype "passive"))
    )
    (net (code "47") (name "Net-(R151-Pad2)") (class "Default")
      (node (ref "R151") (pin "2") (pinfunction "2_2") (pintype "passive"))
      (node (ref "R155") (pin "1") (pinfunction "1_1") (pintype "passive"))
    )
    (net (code "48") (name "Net-(R153-Pad2)") (class "Default")
      (node (ref "R153") (pin "2") (pinfunction "2_2") (pintype "passive"))
      (node (ref "R157") (pin "1") (pinfunction "1_1") (pintype "passive"))
    )
    (net (code "49") (name "Net-(R154-Pad2)") (class "Default")
      (node (ref "R154") (pin "2") (pinfunction "2_2") (pintype "passive"))
      (node (ref "R158") (pin "1") (pinfunction "1_1") (pintype "passive"))
    )
    (net (code "50") (name "Net-(R155-Pad2)") (class "Default")
      (node (ref "R155") (pin "2") (pinfunction "2_2") (pintype "passive"))
      (node (ref "R159") (pin "1") (pinfunction "1_1") (pintype "passive"))
    )
    (net (code "51") (name "Net-(R157-Pad2)") (class "Default")
      (node (ref "R157") (pin "2") (pinfunction "2_2") (pintype "passive"))
      (node (ref "R161") (pin "1") (pinfunction "1_1") (pintype "passive"))
    )
    (net (code "52") (name "Net-(R158-Pad2)") (class "Default")
      (node (ref "R158") (pin "2") (pinfunction "2_2") (pintype "passive"))
      (node (ref "R162") (pin "1") (pinfunction "1_1") (pintype "passive"))
    )
    (net (code "53") (name "Net-(R159-Pad2)") (class "Default")
      (node (ref "R159") (pin "2") (pinfunction "2_2") (pintype "passive"))
      (node (ref "R163") (pin "1") (pinfunction "1_1") (pintype "passive"))
    )
    (net (code "54") (name "Net-(R161-Pad2)") (class "Default")
      (node (ref "R161") (pin "2") (pinfunction "2_2") (pintype "passive"))
      (node (ref "R165") (pin "1") (pinfunction "1_1") (pintype "passive"))
    )
    (net (code "55") (name "Net-(R162-Pad2)") (class "Default")
      (node (ref "R162") (pin "2") (pinfunction "2_2") (pintype "passive"))
      (node (ref "R166") (pin "1") (pinfunction "1_1") (pintype "passive"))
    )
    (net (code "56") (name "Net-(R163-Pad2)") (class "Default")
      (node (ref "R163") (pin "2") (pinfunction "2_2") (pintype "passive"))
      (node (ref "R167") (pin "1") (pinfunction "1_1") (pintype "passive"))
    )
    (net (code "57") (name "Net-(R165-Pad2)") (class "Default")
      (node (ref "R165") (pin "2") (pinfunction "2_2") (pintype "passive"))
      (node (ref "R169") (pin "1") (pinfunction "1_1") (pintype "passive"))
    )
    (net (code "58") (name "Net-(R166-Pad2)") (class "Default")
      (node (ref "R166") (pin "2") (pinfunction "2_2") (pintype "passive"))
      (node (ref "R170") (pin "1") (pinfunction "1_1") (pintype "passive"))
    )
    (net (code "59") (name "Net-(R167-Pad2)") (class "Default")
      (node (ref "R167") (pin "2") (pinfunction "2_2") (pintype "passive"))
      (node (ref "R171") (pin "1") (pinfunction "1_1") (pintype "passive"))
    )
    (net (code "60") (name "Net-(U1-+IN)") (class "Default")
      (node (ref "R37") (pin "2") (pinfunction "2_2") (pintype "passive"))
      (node (ref "U1") (pin "3") (pinfunction "+IN_3") (pintype "input"))
    )
    (net (code "61") (name "Net-(U1--IN)") (class "Default")
      (node (ref "R180") (pin "2") (pinfunction "2_2") (pintype "passive"))
      (node (ref "U1") (pin "4") (pinfunction "-IN_4") (pintype "input"))
    )
    (net (code "62") (name "Net-(U1-OUT)") (class "Default")
      (node (ref "C120") (pin "2") (pinfunction "2_2") (pintype "passive"))
      (node (ref "R179") (pin "2") (pinfunction "2_2") (pintype "passive"))
      (node (ref "R57") (pin "1") (pinfunction "1_1") (pintype "passive"))
      (node (ref "U1") (pin "1") (pinfunction "OUT_1") (pintype "output"))
    )
    (net (code "63") (name "Net-(U2-+IN)") (class "Default")
      (node (ref "R39") (pin "2") (pinfunction "2_2") (pintype "passive"))
      (node (ref "U2") (pin "3") (pinfunction "+IN_3") (pintype "input"))
    )
    (net (code "64") (name "Net-(U2--IN)") (class "Default")
      (node (ref "R178") (pin "2") (pinfunction "2_2") (pintype "passive"))
      (node (ref "U2") (pin "4") (pinfunction "-IN_4") (pintype "input"))
    )
    (net (code "65") (name "Net-(U2-OUT)") (class "Default")
      (node (ref "C119") (pin "2") (pinfunction "2_2") (pintype "passive"))
      (node (ref "R177") (pin "1") (pinfunction "1_1") (pintype "passive"))
      (node (ref "R55") (pin "1") (pinfunction "1_1") (pintype "passive"))
      (node (ref "U2") (pin "1") (pinfunction "OUT_1") (pintype "output"))
    )
    (net (code "66") (name "Net-(U3-+IN)") (class "Default")
      (node (ref "R41") (pin "2") (pinfunction "2_2") (pintype "passive"))
      (node (ref "U3") (pin "3") (pinfunction "+IN_3") (pintype "input"))
    )
    (net (code "67") (name "Net-(U3--IN)") (class "Default")
      (node (ref "R176") (pin "2") (pinfunction "2_2") (pintype "passive"))
      (node (ref "U3") (pin "4") (pinfunction "-IN_4") (pintype "input"))
    )
    (net (code "68") (name "Net-(U3-OUT)") (class "Default")
      (node (ref "C118") (pin "2") (pinfunction "2_2") (pintype "passive"))
      (node (ref "R175") (pin "1") (pinfunction "1_1") (pintype "passive"))
      (node (ref "R50") (pin "1") (pinfunction "1_1") (pintype "passive"))
      (node (ref "U3") (pin "1") (pinfunction "OUT_1") (pintype "output"))
    )
    (net (code "69") (name "Net-(U4-+IN)") (class "Default")
      (node (ref "R43") (pin "2") (pinfunction "2_2") (pintype "passive"))
      (node (ref "U4") (pin "3") (pinfunction "+IN_3") (pintype "input"))
    )
    (net (code "70") (name "Net-(U4--IN)") (class "Default")
      (node (ref "R174") (pin "2") (pinfunction "2_2") (pintype "passive"))
      (node (ref "U4") (pin "4") (pinfunction "-IN_4") (pintype "input"))
    )
    (net (code "71") (name "Net-(U4-OUT)") (class "Default")
      (node (ref "C117") (pin "2") (pinfunction "2_2") (pintype "passive"))
      (node (ref "R173") (pin "1") (pinfunction "1_1") (pintype "passive"))
      (node (ref "R45") (pin "1") (pinfunction "1_1") (pintype "passive"))
      (node (ref "U4") (pin "1") (pinfunction "OUT_1") (pintype "output"))
    )
    (net (code "72") (name "VDC_MEAS") (class "Default")
      (node (ref "C132") (pin "1") (pinfunction "1_1") (pintype "passive"))
      (node (ref "R57") (pin "2") (pinfunction "2_2") (pintype "passive"))
    )
    (net (code "73") (name "VU_MEAS") (class "Default")
      (node (ref "C124") (pin "1") (pinfunction "1_1") (pintype "passive"))
      (node (ref "R45") (pin "2") (pinfunction "2_2") (pintype "passive"))
    )
    (net (code "74") (name "VV_MEAS") (class "Default")
      (node (ref "C125") (pin "1") (pinfunction "1_1") (pintype "passive"))
      (node (ref "R50") (pin "2") (pinfunction "2_2") (pintype "passive"))
    )
    (net (code "75") (name "VW_MEAS") (class "Default")
      (node (ref "C127") (pin "1") (pinfunction "1_1") (pintype "passive"))
      (node (ref "R55") (pin "2") (pinfunction "2_2") (pintype "passive"))
    )
  )
)
